# LNC.net
KiCad netlist of a schematic drawn in EAGLE
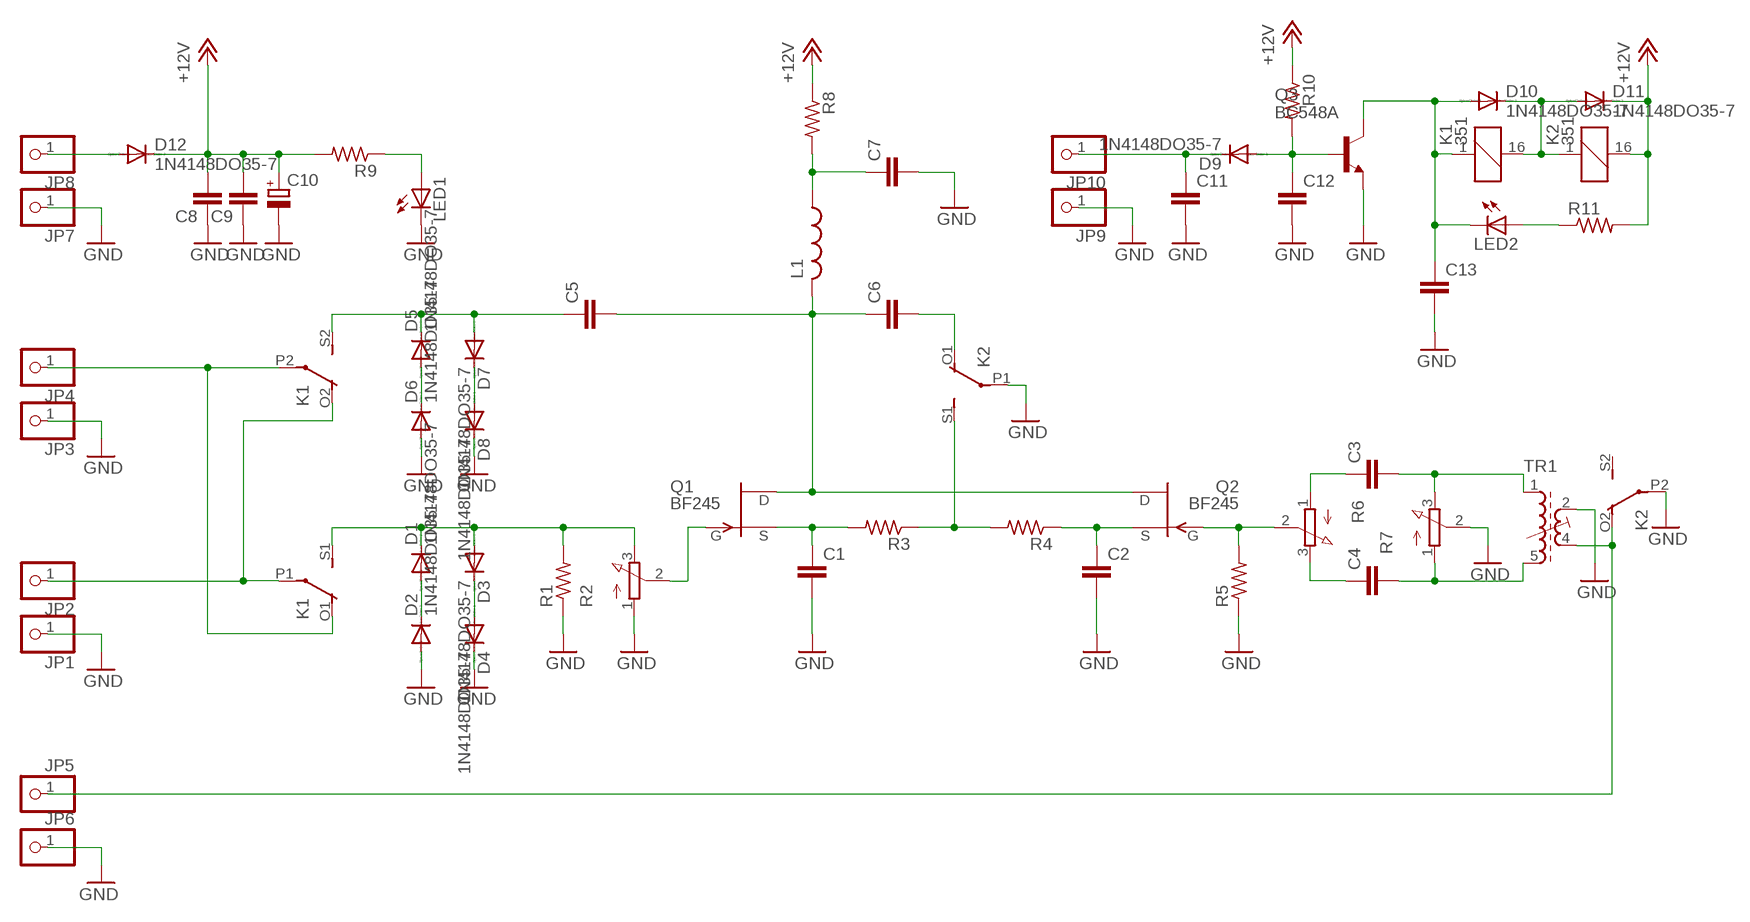
[diagram p0: schematic, sheet 1]

(export (version "E")
  (design (tool "Eeschema 10.0.6"))
  (components
    (comp (ref "C1")
      (value "C-EU050-030X075")
      (footprint "eagle-import:C050-030X075")
      (libsource (lib "eagle-import") (part "C-EU050-030X075"))
    )
    (comp (ref "C2")
      (value "C-EU050-030X075")
      (footprint "eagle-import:C050-030X075")
      (libsource (lib "eagle-import") (part "C-EU050-030X075"))
    )
    (comp (ref "C3")
      (value "C-EU050-030X075")
      (footprint "eagle-import:C050-030X075")
      (libsource (lib "eagle-import") (part "C-EU050-030X075"))
    )
    (comp (ref "C4")
      (value "C-EU050-030X075")
      (footprint "eagle-import:C050-030X075")
      (libsource (lib "eagle-import") (part "C-EU050-030X075"))
    )
    (comp (ref "C5")
      (value "C-EU050-030X075")
      (footprint "eagle-import:C050-030X075")
      (libsource (lib "eagle-import") (part "C-EU050-030X075"))
    )
    (comp (ref "C6")
      (value "C-EU050-030X075")
      (footprint "eagle-import:C050-030X075")
      (libsource (lib "eagle-import") (part "C-EU050-030X075"))
    )
    (comp (ref "C7")
      (value "C-EU050-030X075")
      (footprint "eagle-import:C050-030X075")
      (libsource (lib "eagle-import") (part "C-EU050-030X075"))
    )
    (comp (ref "C8")
      (value "C-EU050-030X075")
      (footprint "eagle-import:C050-030X075")
      (libsource (lib "eagle-import") (part "C-EU050-030X075"))
    )
    (comp (ref "C9")
      (value "C-EU050-030X075")
      (footprint "eagle-import:C050-030X075")
      (libsource (lib "eagle-import") (part "C-EU050-030X075"))
    )
    (comp (ref "C10")
      (value "CPOL-EUE2.5-7")
      (footprint "eagle-import:E2,5-7")
      (libsource (lib "eagle-import") (part "CPOL-EUE2.5-7"))
    )
    (comp (ref "C11")
      (value "C-EU050-030X075")
      (footprint "eagle-import:C050-030X075")
      (libsource (lib "eagle-import") (part "C-EU050-030X075"))
    )
    (comp (ref "C12")
      (value "C-EU050-030X075")
      (footprint "eagle-import:C050-030X075")
      (libsource (lib "eagle-import") (part "C-EU050-030X075"))
    )
    (comp (ref "C13")
      (value "C-EU050-030X075")
      (footprint "eagle-import:C050-030X075")
      (libsource (lib "eagle-import") (part "C-EU050-030X075"))
    )
    (comp (ref "D1")
      (value "1N4148DO35-7")
      (footprint "eagle-import:DO35-7")
      (libsource (lib "eagle-import") (part "1N4148DO35-7"))
    )
    (comp (ref "D2")
      (value "1N4148DO35-7")
      (footprint "eagle-import:DO35-7")
      (libsource (lib "eagle-import") (part "1N4148DO35-7"))
    )
    (comp (ref "D3")
      (value "1N4148DO35-7")
      (footprint "eagle-import:DO35-7")
      (libsource (lib "eagle-import") (part "1N4148DO35-7"))
    )
    (comp (ref "D4")
      (value "1N4148DO35-7")
      (footprint "eagle-import:DO35-7")
      (libsource (lib "eagle-import") (part "1N4148DO35-7"))
    )
    (comp (ref "D5")
      (value "1N4148DO35-7")
      (footprint "eagle-import:DO35-7")
      (libsource (lib "eagle-import") (part "1N4148DO35-7"))
    )
    (comp (ref "D6")
      (value "1N4148DO35-7")
      (footprint "eagle-import:DO35-7")
      (libsource (lib "eagle-import") (part "1N4148DO35-7"))
    )
    (comp (ref "D7")
      (value "1N4148DO35-7")
      (footprint "eagle-import:DO35-7")
      (libsource (lib "eagle-import") (part "1N4148DO35-7"))
    )
    (comp (ref "D8")
      (value "1N4148DO35-7")
      (footprint "eagle-import:DO35-7")
      (libsource (lib "eagle-import") (part "1N4148DO35-7"))
    )
    (comp (ref "D9")
      (value "1N4148DO35-7")
      (footprint "eagle-import:DO35-7")
      (libsource (lib "eagle-import") (part "1N4148DO35-7"))
    )
    (comp (ref "D10")
      (value "1N4148DO35-7")
      (footprint "eagle-import:DO35-7")
      (libsource (lib "eagle-import") (part "1N4148DO35-7"))
    )
    (comp (ref "D11")
      (value "1N4148DO35-7")
      (footprint "eagle-import:DO35-7")
      (libsource (lib "eagle-import") (part "1N4148DO35-7"))
    )
    (comp (ref "D12")
      (value "1N4148DO35-7")
      (footprint "eagle-import:DO35-7")
      (libsource (lib "eagle-import") (part "1N4148DO35-7"))
    )
    (comp (ref "JP1")
      (value "PINHD-1X1")
      (footprint "eagle-import:1X01")
      (libsource (lib "eagle-import") (part "PINHD-1X1"))
    )
    (comp (ref "JP2")
      (value "PINHD-1X1")
      (footprint "eagle-import:1X01")
      (libsource (lib "eagle-import") (part "PINHD-1X1"))
    )
    (comp (ref "JP3")
      (value "PINHD-1X1")
      (footprint "eagle-import:1X01")
      (libsource (lib "eagle-import") (part "PINHD-1X1"))
    )
    (comp (ref "JP4")
      (value "PINHD-1X1")
      (footprint "eagle-import:1X01")
      (libsource (lib "eagle-import") (part "PINHD-1X1"))
    )
    (comp (ref "JP5")
      (value "PINHD-1X1")
      (footprint "eagle-import:1X01")
      (libsource (lib "eagle-import") (part "PINHD-1X1"))
    )
    (comp (ref "JP6")
      (value "PINHD-1X1")
      (footprint "eagle-import:1X01")
      (libsource (lib "eagle-import") (part "PINHD-1X1"))
    )
    (comp (ref "JP7")
      (value "PINHD-1X1")
      (footprint "eagle-import:1X01")
      (libsource (lib "eagle-import") (part "PINHD-1X1"))
    )
    (comp (ref "JP8")
      (value "PINHD-1X1")
      (footprint "eagle-import:1X01")
      (libsource (lib "eagle-import") (part "PINHD-1X1"))
    )
    (comp (ref "JP9")
      (value "PINHD-1X1")
      (footprint "eagle-import:1X01")
      (libsource (lib "eagle-import") (part "PINHD-1X1"))
    )
    (comp (ref "JP10")
      (value "PINHD-1X1")
      (footprint "eagle-import:1X01")
      (libsource (lib "eagle-import") (part "PINHD-1X1"))
    )
    (comp (ref "K1")
      (value "351")
      (footprint "eagle-import:351")
      (libsource (lib "eagle-import") (part "351"))
    )
    (comp (ref "K2")
      (value "351")
      (footprint "eagle-import:351")
      (libsource (lib "eagle-import") (part "351"))
    )
    (comp (ref "L1")
      (value "L-US0207/10")
      (footprint "eagle-import:0207_10")
      (libsource (lib "eagle-import") (part "L-US0207/10"))
    )
    (comp (ref "LED1")
      (value "LED3MM")
      (footprint "eagle-import:LED3MM")
      (libsource (lib "eagle-import") (part "LED3MM"))
    )
    (comp (ref "LED2")
      (value "LED3MM")
      (footprint "eagle-import:LED3MM")
      (libsource (lib "eagle-import") (part "LED3MM"))
    )
    (comp (ref "Q1")
      (value "BF245")
      (footprint "eagle-import:TO92")
      (libsource (lib "eagle-import") (part "BF245"))
    )
    (comp (ref "Q2")
      (value "BF245")
      (footprint "eagle-import:TO92")
      (libsource (lib "eagle-import") (part "BF245"))
    )
    (comp (ref "Q3")
      (value "BC548A")
      (footprint "eagle-import:TO92-EBC")
      (libsource (lib "eagle-import") (part "BC548A"))
    )
    (comp (ref "R1")
      (value "R-US_0204/7")
      (footprint "eagle-import:0204_7")
      (libsource (lib "eagle-import") (part "R-US_0204/7"))
    )
    (comp (ref "R2")
      (value "3RP/1610N")
      (footprint "eagle-import:3RP_1610N")
      (libsource (lib "eagle-import") (part "3RP/1610N"))
    )
    (comp (ref "R3")
      (value "R-US_0204/7")
      (footprint "eagle-import:0204_7")
      (libsource (lib "eagle-import") (part "R-US_0204/7"))
    )
    (comp (ref "R4")
      (value "R-US_0204/7")
      (footprint "eagle-import:0204_7")
      (libsource (lib "eagle-import") (part "R-US_0204/7"))
    )
    (comp (ref "R5")
      (value "R-US_0204/7")
      (footprint "eagle-import:0204_7")
      (libsource (lib "eagle-import") (part "R-US_0204/7"))
    )
    (comp (ref "R6")
      (value "3RP/1610N")
      (footprint "eagle-import:3RP_1610N")
      (libsource (lib "eagle-import") (part "3RP/1610N"))
    )
    (comp (ref "R7")
      (value "3RP/1610N")
      (footprint "eagle-import:3RP_1610N")
      (libsource (lib "eagle-import") (part "3RP/1610N"))
    )
    (comp (ref "R8")
      (value "R-US_0204/7")
      (footprint "eagle-import:0204_7")
      (libsource (lib "eagle-import") (part "R-US_0204/7"))
    )
    (comp (ref "R9")
      (value "R-US_0204/7")
      (footprint "eagle-import:0204_7")
      (libsource (lib "eagle-import") (part "R-US_0204/7"))
    )
    (comp (ref "R10")
      (value "R-US_0204/7")
      (footprint "eagle-import:0204_7")
      (libsource (lib "eagle-import") (part "R-US_0204/7"))
    )
    (comp (ref "R11")
      (value "R-US_0204/7")
      (footprint "eagle-import:0204_7")
      (libsource (lib "eagle-import") (part "R-US_0204/7"))
    )
    (comp (ref "TR1")
      (value "71-4-1542")
      (footprint "eagle-import:71-5")
      (libsource (lib "eagle-import") (part "71-4-1542"))
    )
  )
  (nets
    (net (code "1") (name "+12V") (class "Default")
      (node (ref "C10") (pin "+") (pinfunction "+_+") (pintype "passive"))
      (node (ref "C8") (pin "2") (pinfunction "2_2") (pintype "passive"))
      (node (ref "C9") (pin "2") (pinfunction "2_2") (pintype "passive"))
      (node (ref "D11") (pin "C") (pinfunction "C_C") (pintype "passive"))
      (node (ref "D12") (pin "C") (pinfunction "C_C") (pintype "passive"))
      (node (ref "K2") (pin "16") (pinfunction "2_16") (pintype "passive"))
      (node (ref "R10") (pin "1") (pinfunction "1_1") (pintype "passive"))
      (node (ref "R11") (pin "2") (pinfunction "2_2") (pintype "passive"))
      (node (ref "R8") (pin "1") (pinfunction "1_1") (pintype "passive"))
      (node (ref "R9") (pin "2") (pinfunction "2_2") (pintype "passive"))
    )
    (net (code "2") (name "GND") (class "Default")
      (node (ref "C1") (pin "2") (pinfunction "2_2") (pintype "passive"))
      (node (ref "C10") (pin "-") (pinfunction "-_-") (pintype "passive"))
      (node (ref "C11") (pin "2") (pinfunction "2_2") (pintype "passive"))
      (node (ref "C12") (pin "2") (pinfunction "2_2") (pintype "passive"))
      (node (ref "C13") (pin "2") (pinfunction "2_2") (pintype "passive"))
      (node (ref "C2") (pin "2") (pinfunction "2_2") (pintype "passive"))
      (node (ref "C7") (pin "2") (pinfunction "2_2") (pintype "passive"))
      (node (ref "C8") (pin "1") (pinfunction "1_1") (pintype "passive"))
      (node (ref "C9") (pin "1") (pinfunction "1_1") (pintype "passive"))
      (node (ref "D2") (pin "A") (pinfunction "A_A") (pintype "passive"))
      (node (ref "D4") (pin "C") (pinfunction "C_C") (pintype "passive"))
      (node (ref "D6") (pin "A") (pinfunction "A_A") (pintype "passive"))
      (node (ref "D8") (pin "C") (pinfunction "C_C") (pintype "passive"))
      (node (ref "JP1") (pin "1") (pinfunction "1_1") (pintype "passive"))
      (node (ref "JP3") (pin "1") (pinfunction "1_1") (pintype "passive"))
      (node (ref "JP6") (pin "1") (pinfunction "1_1") (pintype "passive"))
      (node (ref "JP7") (pin "1") (pinfunction "1_1") (pintype "passive"))
      (node (ref "JP9") (pin "1") (pinfunction "1_1") (pintype "passive"))
      (node (ref "K2") (pin "P1") (pinfunction "P_P1") (pintype "passive"))
      (node (ref "K2") (pin "P2") (pinfunction "P_P2") (pintype "passive"))
      (node (ref "LED1") (pin "K") (pinfunction "C_K") (pintype "passive"))
      (node (ref "Q3") (pin "E") (pinfunction "E_E") (pintype "passive"))
      (node (ref "R1") (pin "1") (pinfunction "1_1") (pintype "passive"))
      (node (ref "R2") (pin "1") (pinfunction "A_1") (pintype "passive"))
      (node (ref "R5") (pin "1") (pinfunction "1_1") (pintype "passive"))
      (node (ref "R7") (pin "2") (pinfunction "S_2") (pintype "passive"))
      (node (ref "TR1") (pin "2") (pinfunction "A2_2") (pintype "passive"))
    )
    (net (code "3") (name "Net-(C7-Pad1)") (class "Default")
      (node (ref "C7") (pin "1") (pinfunction "1_1") (pintype "passive"))
      (node (ref "L1") (pin "1") (pinfunction "1_1") (pintype "passive"))
      (node (ref "R8") (pin "2") (pinfunction "2_2") (pintype "passive"))
    )
    (net (code "4") (name "Net-(C11-Pad1)") (class "Default")
      (node (ref "C11") (pin "1") (pinfunction "1_1") (pintype "passive"))
      (node (ref "D9") (pin "C") (pinfunction "C_C") (pintype "passive"))
      (node (ref "JP10") (pin "1") (pinfunction "1_1") (pintype "passive"))
    )
    (net (code "5") (name "Net-(C12-Pad1)") (class "Default")
      (node (ref "C12") (pin "1") (pinfunction "1_1") (pintype "passive"))
      (node (ref "D9") (pin "A") (pinfunction "A_A") (pintype "passive"))
      (node (ref "Q3") (pin "B") (pinfunction "B_B") (pintype "passive"))
      (node (ref "R10") (pin "2") (pinfunction "2_2") (pintype "passive"))
    )
    (net (code "6") (name "Net-(D1-PadA)") (class "Default")
      (node (ref "D1") (pin "A") (pinfunction "A_A") (pintype "passive"))
      (node (ref "D2") (pin "C") (pinfunction "C_C") (pintype "passive"))
    )
    (net (code "7") (name "Net-(D3-PadC)") (class "Default")
      (node (ref "D3") (pin "C") (pinfunction "C_C") (pintype "passive"))
      (node (ref "D4") (pin "A") (pinfunction "A_A") (pintype "passive"))
    )
    (net (code "8") (name "Net-(D5-PadA)") (class "Default")
      (node (ref "D5") (pin "A") (pinfunction "A_A") (pintype "passive"))
      (node (ref "D6") (pin "C") (pinfunction "C_C") (pintype "passive"))
    )
    (net (code "9") (name "Net-(D7-PadC)") (class "Default")
      (node (ref "D7") (pin "C") (pinfunction "C_C") (pintype "passive"))
      (node (ref "D8") (pin "A") (pinfunction "A_A") (pintype "passive"))
    )
    (net (code "10") (name "Net-(D12-PadA)") (class "Default")
      (node (ref "D12") (pin "A") (pinfunction "A_A") (pintype "passive"))
      (node (ref "JP8") (pin "1") (pinfunction "1_1") (pintype "passive"))
    )
    (net (code "11") (name "Net-(K1A-2)") (class "Default")
      (node (ref "D10") (pin "C") (pinfunction "C_C") (pintype "passive"))
      (node (ref "D11") (pin "A") (pinfunction "A_A") (pintype "passive"))
      (node (ref "K1") (pin "16") (pinfunction "2_16") (pintype "passive"))
      (node (ref "K2") (pin "1") (pinfunction "1_1") (pintype "passive"))
    )
    (net (code "12") (name "Net-(K1B-O)") (class "Default")
      (node (ref "JP4") (pin "1") (pinfunction "1_1") (pintype "passive"))
      (node (ref "K1") (pin "O1") (pinfunction "O_O1") (pintype "passive"))
      (node (ref "K1") (pin "P2") (pinfunction "P_P2") (pintype "passive"))
    )
    (net (code "13") (name "Net-(K1B-P)") (class "Default")
      (node (ref "JP2") (pin "1") (pinfunction "1_1") (pintype "passive"))
      (node (ref "K1") (pin "O2") (pinfunction "O_O2") (pintype "passive"))
      (node (ref "K1") (pin "P1") (pinfunction "P_P1") (pintype "passive"))
    )
    (net (code "14") (name "Net-(K1B-S)") (class "Default")
      (node (ref "D1") (pin "C") (pinfunction "C_C") (pintype "passive"))
      (node (ref "D3") (pin "A") (pinfunction "A_A") (pintype "passive"))
      (node (ref "K1") (pin "S1") (pinfunction "S_S1") (pintype "passive"))
      (node (ref "R1") (pin "2") (pinfunction "2_2") (pintype "passive"))
      (node (ref "R2") (pin "3") (pinfunction "E_3") (pintype "passive"))
    )
    (net (code "15") (name "Net-(K1C-S)") (class "Default")
      (node (ref "C5") (pin "1") (pinfunction "1_1") (pintype "passive"))
      (node (ref "D5") (pin "C") (pinfunction "C_C") (pintype "passive"))
      (node (ref "D7") (pin "A") (pinfunction "A_A") (pintype "passive"))
      (node (ref "K1") (pin "S2") (pinfunction "S_S2") (pintype "passive"))
    )
    (net (code "16") (name "Net-(K2B-O)") (class "Default")
      (node (ref "C6") (pin "2") (pinfunction "2_2") (pintype "passive"))
      (node (ref "K2") (pin "O1") (pinfunction "O_O1") (pintype "passive"))
    )
    (net (code "17") (name "Net-(K2B-S)") (class "Default")
      (node (ref "K2") (pin "S1") (pinfunction "S_S1") (pintype "passive"))
      (node (ref "R3") (pin "1") (pinfunction "1_1") (pintype "passive"))
      (node (ref "R4") (pin "2") (pinfunction "2_2") (pintype "passive"))
    )
    (net (code "18") (name "Net-(K2C-O)") (class "Default")
      (node (ref "JP5") (pin "1") (pinfunction "1_1") (pintype "passive"))
      (node (ref "K2") (pin "O2") (pinfunction "O_O2") (pintype "passive"))
      (node (ref "TR1") (pin "4") (pinfunction "E2_4") (pintype "passive"))
    )
    (net (code "19") (name "Net-(LED1-PadA)") (class "Default")
      (node (ref "LED1") (pin "A") (pinfunction "A_A") (pintype "passive"))
      (node (ref "R9") (pin "1") (pinfunction "1_1") (pintype "passive"))
    )
    (net (code "20") (name "Net-(LED2-C)") (class "Default")
      (node (ref "C13") (pin "1") (pinfunction "1_1") (pintype "passive"))
      (node (ref "D10") (pin "A") (pinfunction "A_A") (pintype "passive"))
      (node (ref "K1") (pin "1") (pinfunction "1_1") (pintype "passive"))
      (node (ref "LED2") (pin "K") (pinfunction "C_K") (pintype "passive"))
      (node (ref "Q3") (pin "C") (pinfunction "C_C") (pintype "passive"))
    )
    (net (code "21") (name "Net-(LED2-PadA)") (class "Default")
      (node (ref "LED2") (pin "A") (pinfunction "A_A") (pintype "passive"))
      (node (ref "R11") (pin "1") (pinfunction "1_1") (pintype "passive"))
    )
    (net (code "22") (name "Net-(Q1-D)") (class "Default")
      (node (ref "C5") (pin "2") (pinfunction "2_2") (pintype "passive"))
      (node (ref "C6") (pin "1") (pinfunction "1_1") (pintype "passive"))
      (node (ref "L1") (pin "2") (pinfunction "2_2") (pintype "passive"))
      (node (ref "Q1") (pin "1") (pinfunction "D_1") (pintype "passive"))
      (node (ref "Q2") (pin "1") (pinfunction "D_1") (pintype "passive"))
    )
    (net (code "23") (name "Net-(Q1-G)") (class "Default")
      (node (ref "Q1") (pin "3") (pinfunction "G_3") (pintype "passive"))
      (node (ref "R2") (pin "2") (pinfunction "S_2") (pintype "passive"))
    )
    (net (code "24") (name "Net-(Q1-S)") (class "Default")
      (node (ref "C1") (pin "1") (pinfunction "1_1") (pintype "passive"))
      (node (ref "Q1") (pin "2") (pinfunction "S_2") (pintype "passive"))
      (node (ref "R3") (pin "2") (pinfunction "2_2") (pintype "passive"))
    )
    (net (code "25") (name "Net-(Q2-G)") (class "Default")
      (node (ref "Q2") (pin "3") (pinfunction "G_3") (pintype "passive"))
      (node (ref "R5") (pin "2") (pinfunction "2_2") (pintype "passive"))
      (node (ref "R6") (pin "2") (pinfunction "S_2") (pintype "passive"))
    )
    (net (code "26") (name "Net-(Q2-S)") (class "Default")
      (node (ref "C2") (pin "1") (pinfunction "1_1") (pintype "passive"))
      (node (ref "Q2") (pin "2") (pinfunction "S_2") (pintype "passive"))
      (node (ref "R4") (pin "1") (pinfunction "1_1") (pintype "passive"))
    )
    (net (code "27") (name "Net-(R6-A)") (class "Default")
      (node (ref "C3") (pin "1") (pinfunction "1_1") (pintype "passive"))
      (node (ref "R6") (pin "1") (pinfunction "A_1") (pintype "passive"))
    )
    (net (code "28") (name "Net-(R6-E)") (class "Default")
      (node (ref "C4") (pin "1") (pinfunction "1_1") (pintype "passive"))
      (node (ref "R6") (pin "3") (pinfunction "E_3") (pintype "passive"))
    )
    (net (code "29") (name "Net-(R7-A)") (class "Default")
      (node (ref "C4") (pin "2") (pinfunction "2_2") (pintype "passive"))
      (node (ref "R7") (pin "1") (pinfunction "A_1") (pintype "passive"))
      (node (ref "TR1") (pin "5") (pinfunction "E1_5") (pintype "passive"))
    )
    (net (code "30") (name "Net-(R7-E)") (class "Default")
      (node (ref "C3") (pin "2") (pinfunction "2_2") (pintype "passive"))
      (node (ref "R7") (pin "3") (pinfunction "E_3") (pintype "passive"))
      (node (ref "TR1") (pin "1") (pinfunction "A1_1") (pintype "passive"))
    )
    (net (code "31") (name "unconnected-(K2C-S-PadS2)") (class "Default")
      (node (ref "K2") (pin "S2") (pinfunction "S_S2") (pintype "passive"))
    )
  )
)
